# Hall_Effect.net
KiCad netlist of a schematic drawn in Altium Designer
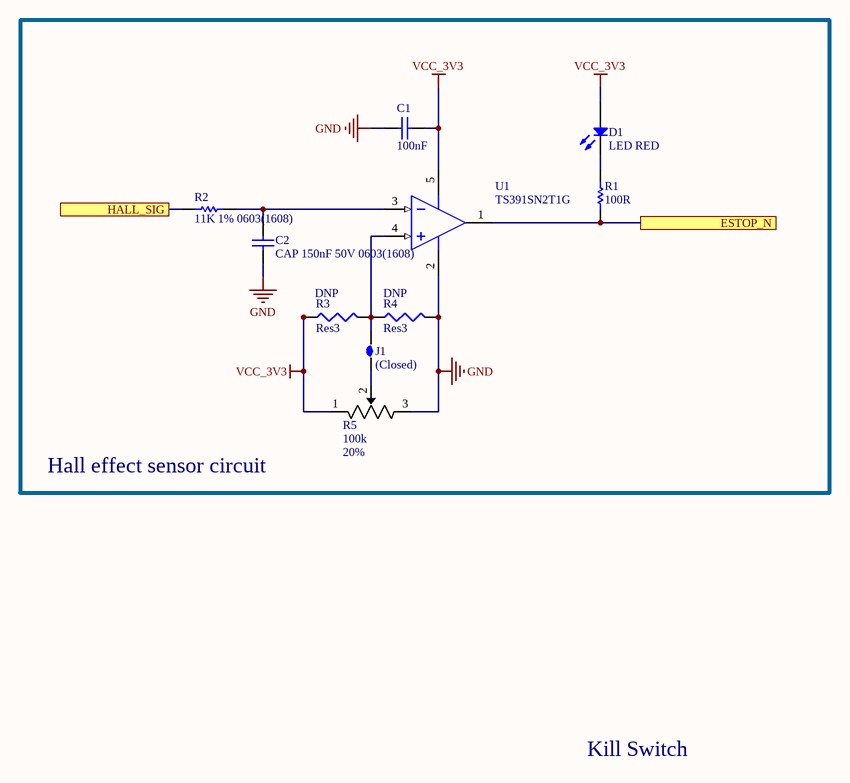
[diagram p0: Hall_Effect.SchDoc]

(export (version "E")
  (design (tool "Eeschema 10.0.6"))
  (components
    (comp (ref "C1")
      (value "100nF")
      (footprint "CAPC0603(1608)100_N")
      (description "CAP 100nF 10V ±10% 0603 (1608 Metric) Thickness 1mm SMD")
      (fields (field (name "TOLERANCE") "Â±10%"))
      (libsource (lib "Altium Content Vault") (part "CMP-1035-02580-1"))
    )
    (comp (ref "C2")
      (value "CAP 150nF 50V 0603(1608)")
      (footprint "CAPC0603(1608)100_M")
      (description "CAP 150nF 50V -20% to +80% 0603 (1608 Metric) Thickness 1mm SMD")
      (fields (field (name "TOLERANCE") "-20% to +80%"))
      (libsource (lib "Altium Content Vault") (part "CAP"))
    )
    (comp (ref "D1")
      (value "LED RED")
      (footprint "LED_0805")
      (description "led")
      (fields
        (field (name "MANUFACTURER") "Lite-On Inc.")
        (field (name "MANUFACTURER PART NUMBER") "LTST-C171KRKT")
      )
      (libsource (lib "CMR_Miscellaneous_Devices") (part "LED0"))
    )
    (comp (ref "J1")
      (value "(Closed)")
      (footprint "Solder Jumper - Closed")
      (description "Jumper")
      (libsource (lib "CMR_PCB_Components") (part "Jumper Closed"))
    )
    (comp (ref "R1")
      (value "100R")
      (footprint "RESC0603(1608)_N")
      (description "100R 0.1W 5% 0603 (1608 Metric)  SMD")
      (fields (field (name "TOLERANCE") "5 %") (field (name "POWER") "0.1 W"))
      (libsource (lib "Altium Content Vault") (part "RES"))
    )
    (comp (ref "R2")
      (value "11K 1% 0603(1608)")
      (footprint "RESC0603(1608)_M")
      (description "11K 0.1W 1% 0603 (1608 Metric)  SMD")
      (fields (field (name "POWER") "0.1 W") (field (name "TOLERANCE") "1 %"))
      (libsource (lib "Altium Content Vault") (part "RES"))
    )
    (comp (ref "R3")
      (value "Res3")
      (footprint "J1-0603")
      (description "Resistor")
      (fields (field (name "ALTIUM_VALUE") "DNP") (field (name "PUBLISHER") "Altium Limited"))
      (libsource (lib "Miscellaneous Devices") (part "Res3"))
    )
    (comp (ref "R4")
      (value "Res3")
      (footprint "J1-0603")
      (description "Resistor")
      (fields (field (name "ALTIUM_VALUE") "DNP") (field (name "PUBLISHER") "Altium Limited"))
      (libsource (lib "Miscellaneous Devices") (part "Res3"))
    )
    (comp (ref "R5")
      (value "100k")
      (footprint "TT BI 22A TRIM POT")
      (description "TT Electronics BI 22AR100KLFTR SMT trim pot, 100k 20%")
      (fields (field (name "TOLERANCE") "20%") (field (name "Comment") "22AR100KLFTR"))
      (libsource (lib "CMR_Resistors_Capacitors_and_Inductors") (part "TT 22AR Trim Pot"))
    )
    (comp (ref "U1")
      (value "TS391SN2T1G")
      (footprint "ONSC-TSOP-5-483-02_V")
      (fields (field (name "MANUFACTURER") "On Semiconductor"))
      (libsource (lib "Altium Content Vault") (part "ONSC-TS391-TSOP-5-483-02"))
    )
  )
  (nets
    (net (code "1") (name "/ESTOP_N") (class "Default")
      (node (ref "R1") (pin "2") (pinfunction "2_2") (pintype "passive"))
      (node (ref "U1") (pin "1") (pinfunction "OUT_1") (pintype "open_collector"))
    )
    (net (code "2") (name "/HALL_SIG") (class "Default")
      (node (ref "R2") (pin "1") (pinfunction "1_1") (pintype "passive"))
    )
    (net (code "3") (name "GND") (class "Default")
      (node (ref "C1") (pin "2") (pinfunction "2_2") (pintype "passive"))
      (node (ref "C2") (pin "1") (pinfunction "1_1") (pintype "passive"))
      (node (ref "R4") (pin "2") (pinfunction "2_2") (pintype "passive"))
      (node (ref "R5") (pin "3") (pinfunction "3_3") (pintype "passive"))
      (node (ref "U1") (pin "2") (pinfunction "VEE_2") (pintype "power_in"))
    )
    (net (code "4") (name "Net-(D1-K)") (class "Default")
      (node (ref "D1") (pin "1") (pinfunction "K_1") (pintype "passive"))
      (node (ref "R1") (pin "1") (pinfunction "1_1") (pintype "passive"))
    )
    (net (code "5") (name "Net-(J1-Pad1)") (class "Default")
      (node (ref "J1") (pin "1") (pinfunction "1_1") (pintype "passive"))
      (node (ref "R5") (pin "2") (pinfunction "2_2") (pintype "passive"))
    )
    (net (code "6") (name "Net-(U1-IN+)") (class "Default")
      (node (ref "J1") (pin "2") (pinfunction "2_2") (pintype "passive"))
      (node (ref "R3") (pin "2") (pinfunction "2_2") (pintype "passive"))
      (node (ref "R4") (pin "1") (pinfunction "1_1") (pintype "passive"))
      (node (ref "U1") (pin "4") (pinfunction "IN+_4") (pintype "input"))
    )
    (net (code "7") (name "Net-(U1-IN-)") (class "Default")
      (node (ref "C2") (pin "2") (pinfunction "2_2") (pintype "passive"))
      (node (ref "R2") (pin "2") (pinfunction "2_2") (pintype "passive"))
      (node (ref "U1") (pin "3") (pinfunction "IN-_3") (pintype "input"))
    )
    (net (code "8") (name "VCC_3V3") (class "Default")
      (node (ref "C1") (pin "1") (pinfunction "1_1") (pintype "passive"))
      (node (ref "D1") (pin "2") (pinfunction "A_2") (pintype "passive"))
      (node (ref "R3") (pin "1") (pinfunction "1_1") (pintype "passive"))
      (node (ref "R5") (pin "1") (pinfunction "1_1") (pintype "passive"))
      (node (ref "U1") (pin "5") (pinfunction "VCC_5") (pintype "power_in"))
    )
  )
)
